# uMultimeter_EXP_Sch.net
KiCad netlist of a schematic drawn in Altium Designer
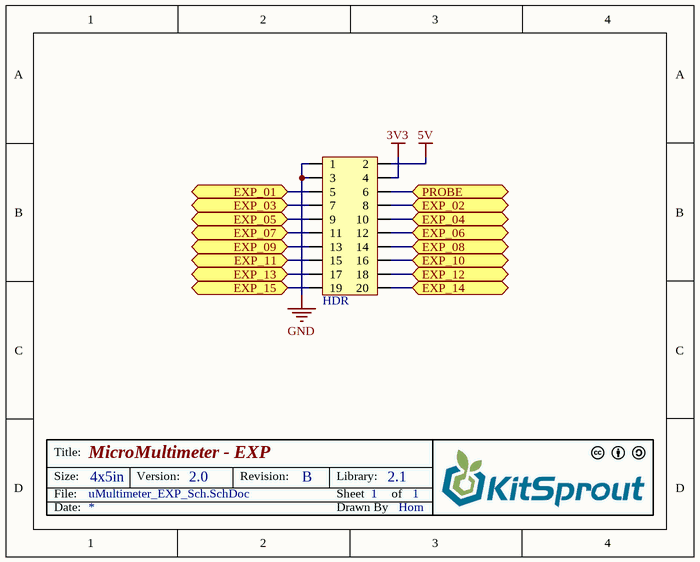
[diagram p0: uMultimeter_EXP_Sch.SchDoc]

(export (version "E")
  (design (tool "Eeschema 10.0.6"))
  (components
    (comp (ref "HDR")
      (value "HDR2x10_2.54")
      (footprint "PCB_ConnectorHDR:HDR2X10_2.54_180HF")
      (description "Header")
      (libsource (lib "SCH_ConnectorHDR") (part "HDR2x10_2.54"))
    )
  )
  (nets
    (net (code "1") (name "/EXP_01") (class "Default")
      (node (ref "HDR") (pin "5") (pinfunction "5_5") (pintype "passive"))
    )
    (net (code "2") (name "/EXP_02") (class "Default")
      (node (ref "HDR") (pin "8") (pinfunction "8_8") (pintype "passive"))
    )
    (net (code "3") (name "/EXP_03") (class "Default")
      (node (ref "HDR") (pin "7") (pinfunction "7_7") (pintype "passive"))
    )
    (net (code "4") (name "/EXP_04") (class "Default")
      (node (ref "HDR") (pin "10") (pinfunction "10_10") (pintype "passive"))
    )
    (net (code "5") (name "/EXP_05") (class "Default")
      (node (ref "HDR") (pin "9") (pinfunction "9_9") (pintype "passive"))
    )
    (net (code "6") (name "/EXP_06") (class "Default")
      (node (ref "HDR") (pin "12") (pinfunction "12_12") (pintype "passive"))
    )
    (net (code "7") (name "/EXP_07") (class "Default")
      (node (ref "HDR") (pin "11") (pinfunction "11_11") (pintype "passive"))
    )
    (net (code "8") (name "/EXP_08") (class "Default")
      (node (ref "HDR") (pin "14") (pinfunction "14_14") (pintype "passive"))
    )
    (net (code "9") (name "/EXP_09") (class "Default")
      (node (ref "HDR") (pin "13") (pinfunction "13_13") (pintype "passive"))
    )
    (net (code "10") (name "/EXP_10") (class "Default")
      (node (ref "HDR") (pin "16") (pinfunction "16_16") (pintype "passive"))
    )
    (net (code "11") (name "/EXP_11") (class "Default")
      (node (ref "HDR") (pin "15") (pinfunction "15_15") (pintype "passive"))
    )
    (net (code "12") (name "/EXP_12") (class "Default")
      (node (ref "HDR") (pin "18") (pinfunction "18_18") (pintype "passive"))
    )
    (net (code "13") (name "/EXP_13") (class "Default")
      (node (ref "HDR") (pin "17") (pinfunction "17_17") (pintype "passive"))
    )
    (net (code "14") (name "/EXP_14") (class "Default")
      (node (ref "HDR") (pin "20") (pinfunction "20_20") (pintype "passive"))
    )
    (net (code "15") (name "/EXP_15") (class "Default")
      (node (ref "HDR") (pin "19") (pinfunction "19_19") (pintype "passive"))
    )
    (net (code "16") (name "/PROBE") (class "Default")
      (node (ref "HDR") (pin "6") (pinfunction "6_6") (pintype "passive"))
    )
    (net (code "17") (name "3V3") (class "Default")
      (node (ref "HDR") (pin "4") (pinfunction "4_4") (pintype "passive"))
    )
    (net (code "18") (name "5V") (class "Default")
      (node (ref "HDR") (pin "2") (pinfunction "2_2") (pintype "passive"))
    )
    (net (code "19") (name "GND") (class "Default")
      (node (ref "HDR") (pin "1") (pinfunction "1_1") (pintype "passive"))
      (node (ref "HDR") (pin "3") (pinfunction "3_3") (pintype "passive"))
    )
  )
)
